# Power_Board_DCDC2.net
KiCad netlist of a schematic drawn in Altium Designer
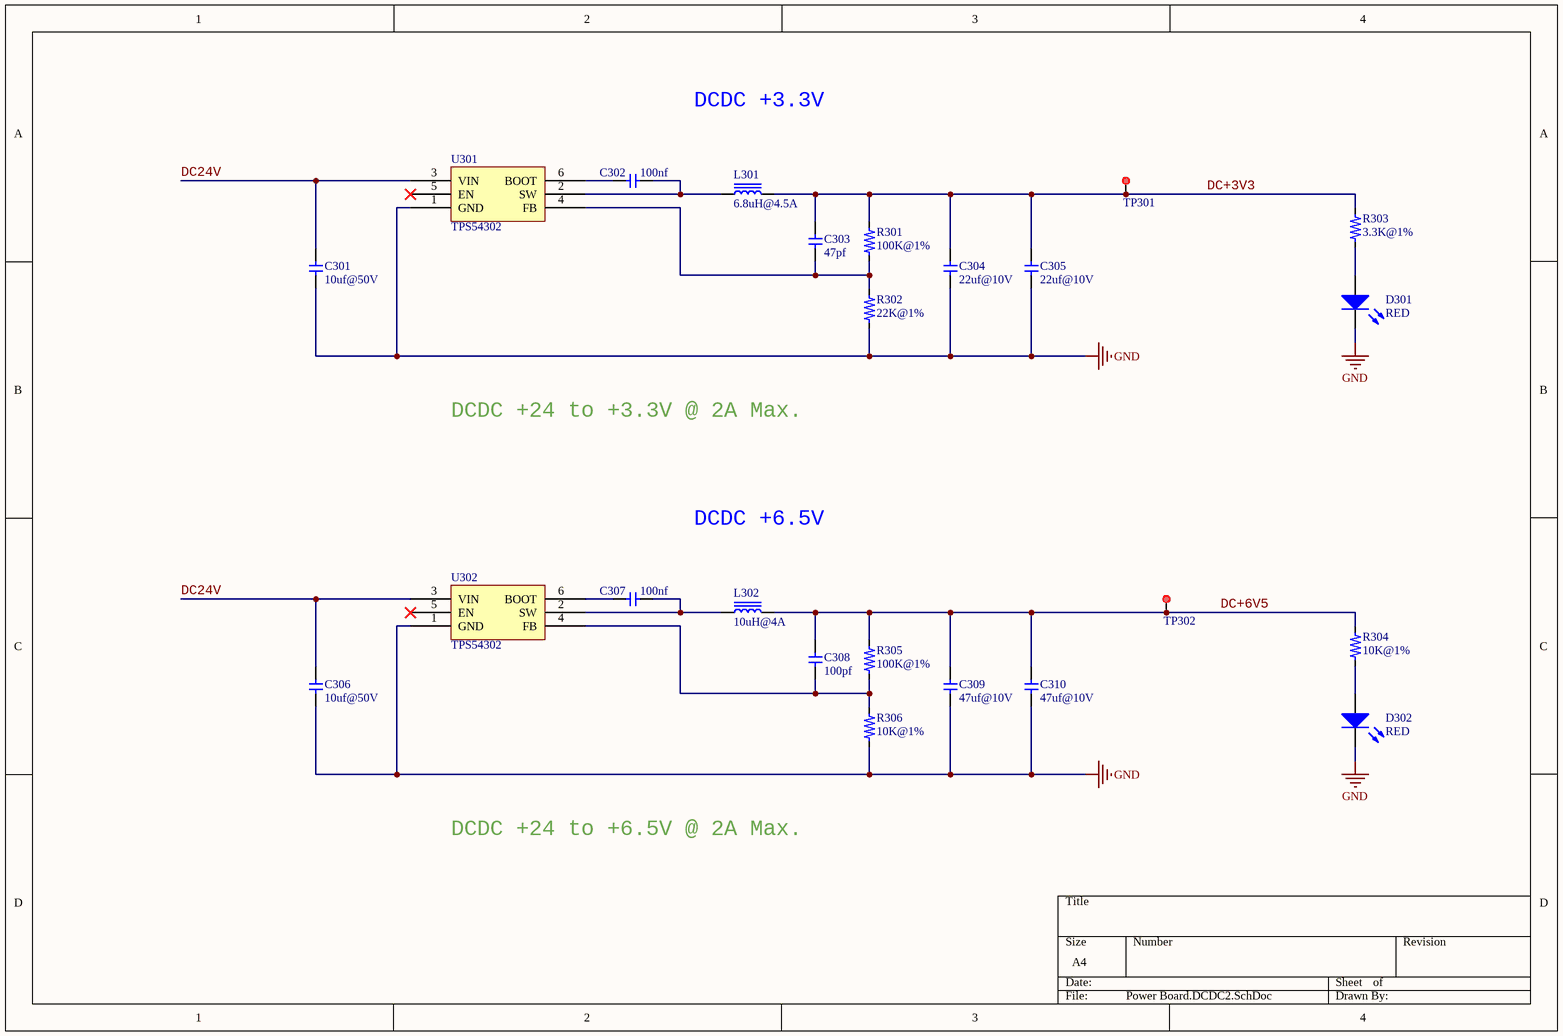
[diagram p0: Power Board.DCDC2.SchDoc]

(export (version "E")
  (design (tool "Eeschema 10.0.6"))
  (components
    (comp (ref "C301")
      (value "10uf@50V")
      (footprint "C1206")
      (fields (field (name "Comment") "Cap"))
      (libsource (lib "carrot_lib") (part "Cap"))
    )
    (comp (ref "C302")
      (value "100nf")
      (footprint "C0603")
      (fields (field (name "Comment") "Cap"))
      (libsource (lib "carrot_lib") (part "Cap"))
    )
    (comp (ref "C303")
      (value "47pf")
      (footprint "C0603")
      (fields (field (name "Comment") "Cap"))
      (libsource (lib "carrot_lib") (part "Cap"))
    )
    (comp (ref "C304")
      (value "22uf@10V")
      (footprint "C1206")
      (fields (field (name "Comment") "Cap"))
      (libsource (lib "carrot_lib") (part "Cap"))
    )
    (comp (ref "C305")
      (value "22uf@10V")
      (footprint "C1206")
      (fields (field (name "Comment") "Cap"))
      (libsource (lib "carrot_lib") (part "Cap"))
    )
    (comp (ref "C306")
      (value "10uf@50V")
      (footprint "C1206")
      (fields (field (name "Comment") "Cap"))
      (libsource (lib "carrot_lib") (part "Cap"))
    )
    (comp (ref "C307")
      (value "100nf")
      (footprint "C0603")
      (fields (field (name "Comment") "Cap"))
      (libsource (lib "carrot_lib") (part "Cap"))
    )
    (comp (ref "C308")
      (value "100pf")
      (footprint "C0603")
      (fields (field (name "Comment") "Cap"))
      (libsource (lib "carrot_lib") (part "Cap"))
    )
    (comp (ref "C309")
      (value "47uf@10V")
      (footprint "C1206")
      (fields (field (name "Comment") "Cap"))
      (libsource (lib "carrot_lib") (part "Cap"))
    )
    (comp (ref "C310")
      (value "47uf@10V")
      (footprint "C1206")
      (fields (field (name "Comment") "Cap"))
      (libsource (lib "carrot_lib") (part "Cap"))
    )
    (comp (ref "D301")
      (value "RED")
      (footprint "LED0603")
      (fields (field (name "Comment") "LED"))
      (libsource (lib "carrot_lib") (part "LED"))
    )
    (comp (ref "D302")
      (value "RED")
      (footprint "LED0603")
      (fields (field (name "Comment") "LED"))
      (libsource (lib "carrot_lib") (part "LED"))
    )
    (comp (ref "L301")
      (value "6.8uH@4.5A")
      (footprint "L06063")
      (description "Magnetic-Core Inductor")
      (fields (field (name "Comment") "Inductor Iron"))
      (libsource (lib "carrot_lib") (part "Inductor Iron"))
    )
    (comp (ref "L302")
      (value "10uH@4A")
      (footprint "L06063")
      (description "Magnetic-Core Inductor")
      (fields (field (name "Comment") "Inductor Iron"))
      (libsource (lib "carrot_lib") (part "Inductor Iron"))
    )
    (comp (ref "R301")
      (value "100K@1%")
      (footprint "R0603")
      (description "电阻")
      (fields (field (name "Comment") "Res"))
      (libsource (lib "carrot_lib") (part "Res"))
    )
    (comp (ref "R302")
      (value "22K@1%")
      (footprint "R0603")
      (description "电阻")
      (fields (field (name "Comment") "Res"))
      (libsource (lib "carrot_lib") (part "Res"))
    )
    (comp (ref "R303")
      (value "3.3K@1%")
      (footprint "R0603")
      (description "电阻")
      (fields (field (name "Comment") "Res"))
      (libsource (lib "carrot_lib") (part "Res"))
    )
    (comp (ref "R304")
      (value "10K@1%")
      (footprint "R0603")
      (description "电阻")
      (fields (field (name "Comment") "Res"))
      (libsource (lib "carrot_lib") (part "Res"))
    )
    (comp (ref "R305")
      (value "100K@1%")
      (footprint "R0603")
      (description "电阻")
      (fields (field (name "Comment") "Res"))
      (libsource (lib "carrot_lib") (part "Res"))
    )
    (comp (ref "R306")
      (value "10K@1%")
      (footprint "R0603")
      (description "电阻")
      (fields (field (name "Comment") "Res"))
      (libsource (lib "carrot_lib") (part "Res"))
    )
    (comp (ref "TP301")
      (value "TestPoint")
      (footprint "TestPoint-THM1.0-L")
      (description "测试点")
      (libsource (lib "carrot_lib") (part "TestPoint"))
    )
    (comp (ref "TP302")
      (value "TestPoint")
      (footprint "TestPoint-THM1.0-L")
      (description "测试点")
      (libsource (lib "carrot_lib") (part "TestPoint"))
    )
    (comp (ref "U301")
      (value "TPS54302")
      (footprint "TPS54302-SOT23-6")
      (description "TPS54302 4.5-V to 28-V Input, 3-A Output, EMI-Friendly Synchronous Step-Down Converter")
      (libsource (lib "carrot_lib") (part "TPS54302"))
    )
    (comp (ref "U302")
      (value "TPS54302")
      (footprint "TPS54302-SOT23-6")
      (description "TPS54302 4.5-V to 28-V Input, 3-A Output, EMI-Friendly Synchronous Step-Down Converter")
      (libsource (lib "carrot_lib") (part "TPS54302"))
    )
  )
  (nets
    (net (code "1") (name "/DC+3V3") (class "Default")
      (node (ref "C303") (pin "1") (pinfunction "1_1") (pintype "passive"))
      (node (ref "C304") (pin "2") (pinfunction "2_2") (pintype "passive"))
      (node (ref "C305") (pin "2") (pinfunction "2_2") (pintype "passive"))
      (node (ref "L301") (pin "2") (pinfunction "2_2") (pintype "passive"))
      (node (ref "R301") (pin "2") (pinfunction "2_2") (pintype "passive"))
      (node (ref "R303") (pin "2") (pinfunction "2_2") (pintype "passive"))
      (node (ref "TP301") (pin "1") (pinfunction "1_1") (pintype "passive"))
    )
    (net (code "2") (name "/DC+6V5") (class "Default")
      (node (ref "C308") (pin "1") (pinfunction "1_1") (pintype "passive"))
      (node (ref "C309") (pin "2") (pinfunction "2_2") (pintype "passive"))
      (node (ref "C310") (pin "2") (pinfunction "2_2") (pintype "passive"))
      (node (ref "L302") (pin "2") (pinfunction "2_2") (pintype "passive"))
      (node (ref "R304") (pin "2") (pinfunction "2_2") (pintype "passive"))
      (node (ref "R305") (pin "2") (pinfunction "2_2") (pintype "passive"))
      (node (ref "TP302") (pin "1") (pinfunction "1_1") (pintype "passive"))
    )
    (net (code "3") (name "/DC24V") (class "Default")
      (node (ref "C301") (pin "2") (pinfunction "2_2") (pintype "passive"))
      (node (ref "C306") (pin "2") (pinfunction "2_2") (pintype "passive"))
      (node (ref "U301") (pin "3") (pinfunction "VIN_3") (pintype "passive"))
      (node (ref "U302") (pin "3") (pinfunction "VIN_3") (pintype "passive"))
    )
    (net (code "4") (name "GND") (class "Default")
      (node (ref "C301") (pin "1") (pinfunction "1_1") (pintype "passive"))
      (node (ref "C304") (pin "1") (pinfunction "1_1") (pintype "passive"))
      (node (ref "C305") (pin "1") (pinfunction "1_1") (pintype "passive"))
      (node (ref "C306") (pin "1") (pinfunction "1_1") (pintype "passive"))
      (node (ref "C309") (pin "1") (pinfunction "1_1") (pintype "passive"))
      (node (ref "C310") (pin "1") (pinfunction "1_1") (pintype "passive"))
      (node (ref "D301") (pin "2") (pinfunction "K_2") (pintype "passive"))
      (node (ref "D302") (pin "2") (pinfunction "K_2") (pintype "passive"))
      (node (ref "R302") (pin "1") (pinfunction "1_1") (pintype "passive"))
      (node (ref "R306") (pin "1") (pinfunction "1_1") (pintype "passive"))
      (node (ref "U301") (pin "1") (pinfunction "GND_1") (pintype "passive"))
      (node (ref "U302") (pin "1") (pinfunction "GND_1") (pintype "passive"))
    )
    (net (code "5") (name "Net-(D301-A)") (class "Default")
      (node (ref "D301") (pin "1") (pinfunction "A_1") (pintype "passive"))
      (node (ref "R303") (pin "1") (pinfunction "1_1") (pintype "passive"))
    )
    (net (code "6") (name "Net-(D302-A)") (class "Default")
      (node (ref "D302") (pin "1") (pinfunction "A_1") (pintype "passive"))
      (node (ref "R304") (pin "1") (pinfunction "1_1") (pintype "passive"))
    )
    (net (code "7") (name "Net-(U301-BOOT)") (class "Default")
      (node (ref "C302") (pin "2") (pinfunction "2_2") (pintype "passive"))
      (node (ref "U301") (pin "6") (pinfunction "BOOT_6") (pintype "passive"))
    )
    (net (code "8") (name "Net-(U301-FB)") (class "Default")
      (node (ref "C303") (pin "2") (pinfunction "2_2") (pintype "passive"))
      (node (ref "R301") (pin "1") (pinfunction "1_1") (pintype "passive"))
      (node (ref "R302") (pin "2") (pinfunction "2_2") (pintype "passive"))
      (node (ref "U301") (pin "4") (pinfunction "FB_4") (pintype "passive"))
    )
    (net (code "9") (name "Net-(U301-SW)") (class "Default")
      (node (ref "C302") (pin "1") (pinfunction "1_1") (pintype "passive"))
      (node (ref "L301") (pin "1") (pinfunction "1_1") (pintype "passive"))
      (node (ref "U301") (pin "2") (pinfunction "SW_2") (pintype "passive"))
    )
    (net (code "10") (name "Net-(U302-BOOT)") (class "Default")
      (node (ref "C307") (pin "2") (pinfunction "2_2") (pintype "passive"))
      (node (ref "U302") (pin "6") (pinfunction "BOOT_6") (pintype "passive"))
    )
    (net (code "11") (name "Net-(U302-FB)") (class "Default")
      (node (ref "C308") (pin "2") (pinfunction "2_2") (pintype "passive"))
      (node (ref "R305") (pin "1") (pinfunction "1_1") (pintype "passive"))
      (node (ref "R306") (pin "2") (pinfunction "2_2") (pintype "passive"))
      (node (ref "U302") (pin "4") (pinfunction "FB_4") (pintype "passive"))
    )
    (net (code "12") (name "Net-(U302-SW)") (class "Default")
      (node (ref "C307") (pin "1") (pinfunction "1_1") (pintype "passive"))
      (node (ref "L302") (pin "1") (pinfunction "1_1") (pintype "passive"))
      (node (ref "U302") (pin "2") (pinfunction "SW_2") (pintype "passive"))
    )
    (net (code "13") (name "unconnected-(U301-EN-Pad5)") (class "Default")
      (node (ref "U301") (pin "5") (pinfunction "EN_5") (pintype "passive+no_connect"))
    )
    (net (code "14") (name "unconnected-(U302-EN-Pad5)") (class "Default")
      (node (ref "U302") (pin "5") (pinfunction "EN_5") (pintype "passive+no_connect"))
    )
  )
)
